# Digital_Input_CPU.net
KiCad netlist of a schematic drawn in Altium Designer
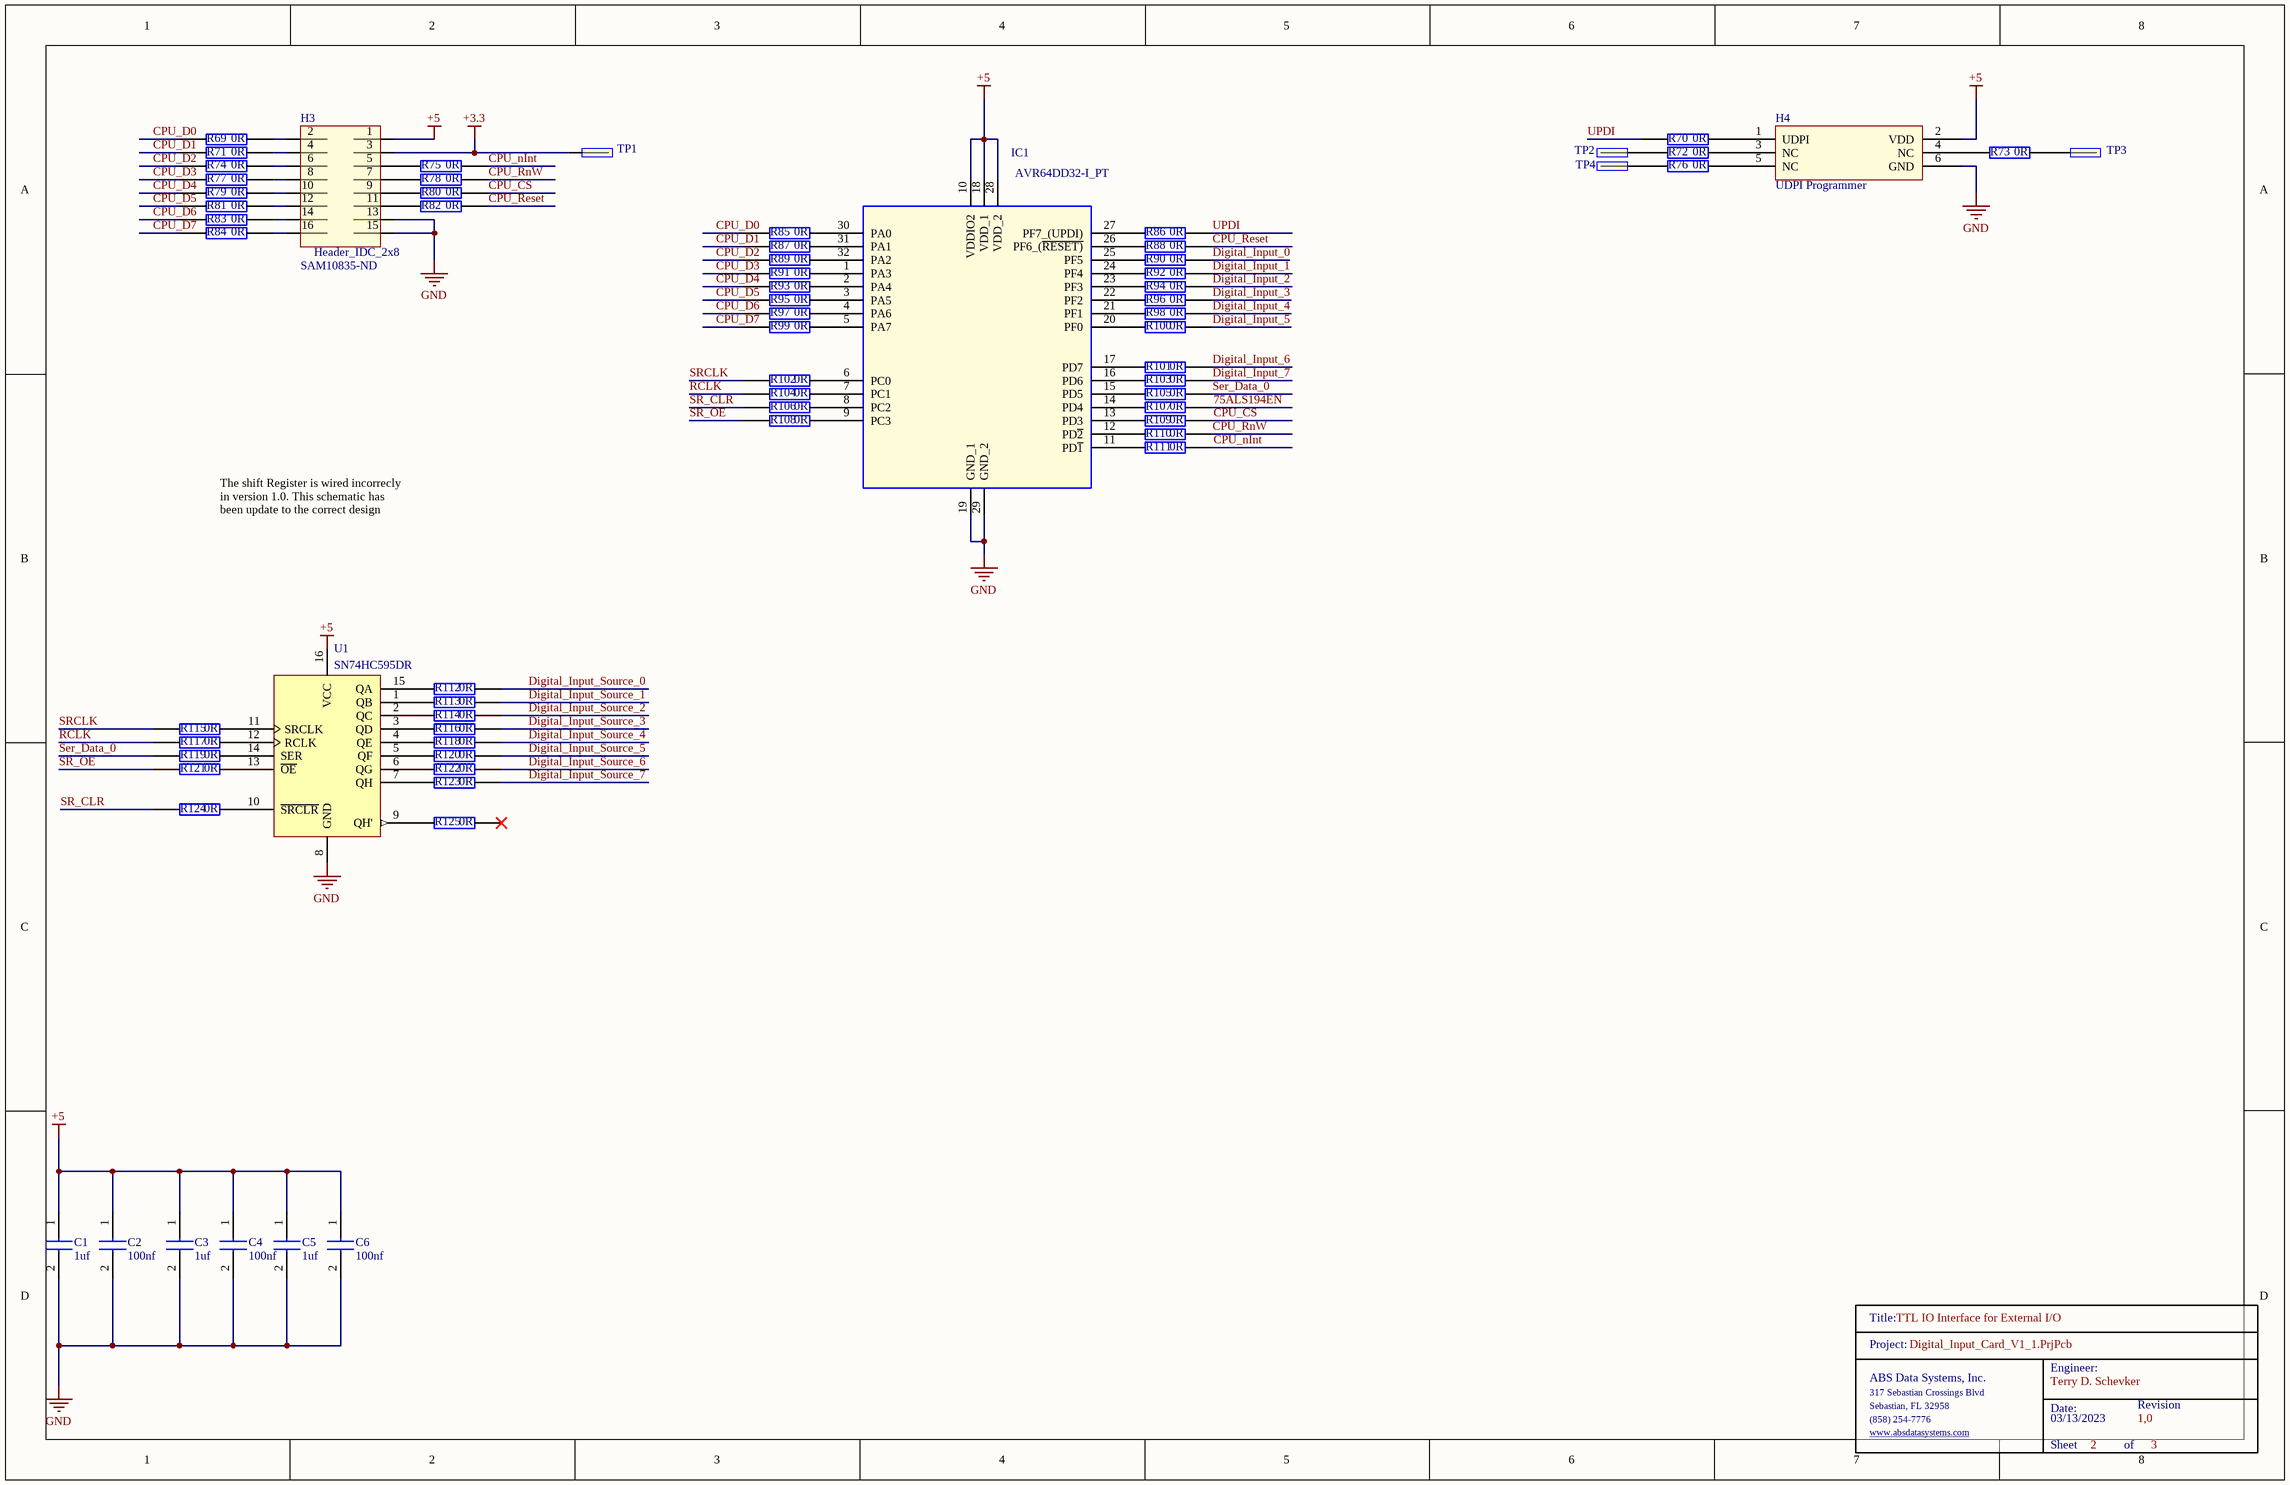
[diagram p0: Digital_Input_CPU.SchDoc]

(export (version "E")
  (design (tool "Eeschema 10.0.6"))
  (components
    (comp (ref "C1")
      (value "1uf")
      (footprint "0603")
      (description "Samsung Electro-Mechanics 0603 1uf")
      (libsource (lib "Capacitors") (part "CL10B105KA8NNNL"))
    )
    (comp (ref "C2")
      (value "100nf")
      (footprint "0603")
      (description "Samsung Electro-Mechanics 0603 100nf")
      (libsource (lib "Capacitors") (part "CL10B104JB8NNNC"))
    )
    (comp (ref "C3")
      (value "1uf")
      (footprint "0603")
      (description "Samsung Electro-Mechanics 0603 1uf")
      (libsource (lib "Capacitors") (part "CL10B105KA8NNNL"))
    )
    (comp (ref "C4")
      (value "100nf")
      (footprint "0603")
      (description "Samsung Electro-Mechanics 0603 100nf")
      (libsource (lib "Capacitors") (part "CL10B104JB8NNNC"))
    )
    (comp (ref "C5")
      (value "1uf")
      (footprint "0603")
      (description "Samsung Electro-Mechanics 0603 1uf")
      (libsource (lib "Capacitors") (part "CL10B105KA8NNNL"))
    )
    (comp (ref "C6")
      (value "100nf")
      (footprint "0603")
      (description "Samsung Electro-Mechanics 0603 100nf")
      (libsource (lib "Capacitors") (part "CL10B104JB8NNNC"))
    )
    (comp (ref "H3")
      (value "Header_IDC_2x8")
      (footprint "HEADER16")
      (description "16 Pin 2x8 Through Hold IDC Connector")
      (fields
        (field (name "MANUFACTURER") "Samtec")
        (field (name "MANUFACTURER PART NUMBER") "TST-108-01-G-D")
        (field (name "SUPPLIER PART NUMBER 1") "SAM10835-ND")
      )
      (libsource (lib "Misc") (part "Header_IDC_2x8"))
    )
    (comp (ref "H4")
      (value "UDPI Programmer")
      (footprint "HDR2X3")
      (description "6 Pin 2X3 Through Hole Header")
      (libsource (lib "Misc") (part "UDPI Programmer"))
    )
    (comp (ref "IC1")
      (value "AVR64DD32-I_PT")
      (footprint "QFP80P900X900X120-32N")
      (description "Integrated Circuit")
      (fields (field (name "MANUFACTURER_PART_NUMBER") "AVR64DD32-I/PT ¦ MULTI-VOLTAGE I/O"))
      (libsource (lib "CPU_Memory") (part "AVR64DD32-I_PT"))
    )
    (comp (ref "R69")
      (value "0R")
      (footprint "0603")
      (description "YAGEO 0603 0 ohm")
      (fields
        (field (name "MOUSER PART NUMBER") "603-RC0603JR-070RL")
        (field (name "MANUFACTURER_PART_NUMBER") "RC0603JR-070RL")
      )
      (libsource (lib "Resistors") (part "RC0603JR-070RL"))
    )
    (comp (ref "R70")
      (value "0R")
      (footprint "0603")
      (description "YAGEO 0603 0 ohm")
      (fields
        (field (name "MOUSER PART NUMBER") "603-RC0603JR-070RL")
        (field (name "MANUFACTURER_PART_NUMBER") "RC0603JR-070RL")
      )
      (libsource (lib "Resistors") (part "RC0603JR-070RL"))
    )
    (comp (ref "R71")
      (value "0R")
      (footprint "0603")
      (description "YAGEO 0603 0 ohm")
      (fields
        (field (name "MOUSER PART NUMBER") "603-RC0603JR-070RL")
        (field (name "MANUFACTURER_PART_NUMBER") "RC0603JR-070RL")
      )
      (libsource (lib "Resistors") (part "RC0603JR-070RL"))
    )
    (comp (ref "R72")
      (value "0R")
      (footprint "0603")
      (description "YAGEO 0603 0 ohm")
      (fields
        (field (name "MOUSER PART NUMBER") "603-RC0603JR-070RL")
        (field (name "MANUFACTURER_PART_NUMBER") "RC0603JR-070RL")
      )
      (libsource (lib "Resistors") (part "RC0603JR-070RL"))
    )
    (comp (ref "R73")
      (value "0R")
      (footprint "0603")
      (description "YAGEO 0603 0 ohm")
      (fields
        (field (name "MOUSER PART NUMBER") "603-RC0603JR-070RL")
        (field (name "MANUFACTURER_PART_NUMBER") "RC0603JR-070RL")
      )
      (libsource (lib "Resistors") (part "RC0603JR-070RL"))
    )
    (comp (ref "R74")
      (value "0R")
      (footprint "0603")
      (description "YAGEO 0603 0 ohm")
      (fields
        (field (name "MOUSER PART NUMBER") "603-RC0603JR-070RL")
        (field (name "MANUFACTURER_PART_NUMBER") "RC0603JR-070RL")
      )
      (libsource (lib "Resistors") (part "RC0603JR-070RL"))
    )
    (comp (ref "R75")
      (value "0R")
      (footprint "0603")
      (description "YAGEO 0603 0 ohm")
      (fields
        (field (name "MOUSER PART NUMBER") "603-RC0603JR-070RL")
        (field (name "MANUFACTURER_PART_NUMBER") "RC0603JR-070RL")
      )
      (libsource (lib "Resistors") (part "RC0603JR-070RL"))
    )
    (comp (ref "R76")
      (value "0R")
      (footprint "0603")
      (description "YAGEO 0603 0 ohm")
      (fields
        (field (name "MOUSER PART NUMBER") "603-RC0603JR-070RL")
        (field (name "MANUFACTURER_PART_NUMBER") "RC0603JR-070RL")
      )
      (libsource (lib "Resistors") (part "RC0603JR-070RL"))
    )
    (comp (ref "R77")
      (value "0R")
      (footprint "0603")
      (description "YAGEO 0603 0 ohm")
      (fields
        (field (name "MOUSER PART NUMBER") "603-RC0603JR-070RL")
        (field (name "MANUFACTURER_PART_NUMBER") "RC0603JR-070RL")
      )
      (libsource (lib "Resistors") (part "RC0603JR-070RL"))
    )
    (comp (ref "R78")
      (value "0R")
      (footprint "0603")
      (description "YAGEO 0603 0 ohm")
      (fields
        (field (name "MOUSER PART NUMBER") "603-RC0603JR-070RL")
        (field (name "MANUFACTURER_PART_NUMBER") "RC0603JR-070RL")
      )
      (libsource (lib "Resistors") (part "RC0603JR-070RL"))
    )
    (comp (ref "R79")
      (value "0R")
      (footprint "0603")
      (description "YAGEO 0603 0 ohm")
      (fields
        (field (name "MOUSER PART NUMBER") "603-RC0603JR-070RL")
        (field (name "MANUFACTURER_PART_NUMBER") "RC0603JR-070RL")
      )
      (libsource (lib "Resistors") (part "RC0603JR-070RL"))
    )
    (comp (ref "R80")
      (value "0R")
      (footprint "0603")
      (description "YAGEO 0603 0 ohm")
      (fields
        (field (name "MOUSER PART NUMBER") "603-RC0603JR-070RL")
        (field (name "MANUFACTURER_PART_NUMBER") "RC0603JR-070RL")
      )
      (libsource (lib "Resistors") (part "RC0603JR-070RL"))
    )
    (comp (ref "R81")
      (value "0R")
      (footprint "0603")
      (description "YAGEO 0603 0 ohm")
      (fields
        (field (name "MOUSER PART NUMBER") "603-RC0603JR-070RL")
        (field (name "MANUFACTURER_PART_NUMBER") "RC0603JR-070RL")
      )
      (libsource (lib "Resistors") (part "RC0603JR-070RL"))
    )
    (comp (ref "R82")
      (value "0R")
      (footprint "0603")
      (description "YAGEO 0603 0 ohm")
      (fields
        (field (name "MOUSER PART NUMBER") "603-RC0603JR-070RL")
        (field (name "MANUFACTURER_PART_NUMBER") "RC0603JR-070RL")
      )
      (libsource (lib "Resistors") (part "RC0603JR-070RL"))
    )
    (comp (ref "R83")
      (value "0R")
      (footprint "0603")
      (description "YAGEO 0603 0 ohm")
      (fields
        (field (name "MOUSER PART NUMBER") "603-RC0603JR-070RL")
        (field (name "MANUFACTURER_PART_NUMBER") "RC0603JR-070RL")
      )
      (libsource (lib "Resistors") (part "RC0603JR-070RL"))
    )
    (comp (ref "R84")
      (value "0R")
      (footprint "0603")
      (description "YAGEO 0603 0 ohm")
      (fields
        (field (name "MOUSER PART NUMBER") "603-RC0603JR-070RL")
        (field (name "MANUFACTURER_PART_NUMBER") "RC0603JR-070RL")
      )
      (libsource (lib "Resistors") (part "RC0603JR-070RL"))
    )
    (comp (ref "R85")
      (value "0R")
      (footprint "0603")
      (description "YAGEO 0603 0 ohm")
      (fields
        (field (name "MOUSER PART NUMBER") "603-RC0603JR-070RL")
        (field (name "MANUFACTURER_PART_NUMBER") "RC0603JR-070RL")
      )
      (libsource (lib "Resistors") (part "RC0603JR-070RL"))
    )
    (comp (ref "R86")
      (value "0R")
      (footprint "0603")
      (description "YAGEO 0603 0 ohm")
      (fields
        (field (name "MOUSER PART NUMBER") "603-RC0603JR-070RL")
        (field (name "MANUFACTURER_PART_NUMBER") "RC0603JR-070RL")
      )
      (libsource (lib "Resistors") (part "RC0603JR-070RL"))
    )
    (comp (ref "R87")
      (value "0R")
      (footprint "0603")
      (description "YAGEO 0603 0 ohm")
      (fields
        (field (name "MOUSER PART NUMBER") "603-RC0603JR-070RL")
        (field (name "MANUFACTURER_PART_NUMBER") "RC0603JR-070RL")
      )
      (libsource (lib "Resistors") (part "RC0603JR-070RL"))
    )
    (comp (ref "R88")
      (value "0R")
      (footprint "0603")
      (description "YAGEO 0603 0 ohm")
      (fields
        (field (name "MOUSER PART NUMBER") "603-RC0603JR-070RL")
        (field (name "MANUFACTURER_PART_NUMBER") "RC0603JR-070RL")
      )
      (libsource (lib "Resistors") (part "RC0603JR-070RL"))
    )
    (comp (ref "R89")
      (value "0R")
      (footprint "0603")
      (description "YAGEO 0603 0 ohm")
      (fields
        (field (name "MOUSER PART NUMBER") "603-RC0603JR-070RL")
        (field (name "MANUFACTURER_PART_NUMBER") "RC0603JR-070RL")
      )
      (libsource (lib "Resistors") (part "RC0603JR-070RL"))
    )
    (comp (ref "R90")
      (value "0R")
      (footprint "0603")
      (description "YAGEO 0603 0 ohm")
      (fields
        (field (name "MOUSER PART NUMBER") "603-RC0603JR-070RL")
        (field (name "MANUFACTURER_PART_NUMBER") "RC0603JR-070RL")
      )
      (libsource (lib "Resistors") (part "RC0603JR-070RL"))
    )
    (comp (ref "R91")
      (value "0R")
      (footprint "0603")
      (description "YAGEO 0603 0 ohm")
      (fields
        (field (name "MOUSER PART NUMBER") "603-RC0603JR-070RL")
        (field (name "MANUFACTURER_PART_NUMBER") "RC0603JR-070RL")
      )
      (libsource (lib "Resistors") (part "RC0603JR-070RL"))
    )
    (comp (ref "R92")
      (value "0R")
      (footprint "0603")
      (description "YAGEO 0603 0 ohm")
      (fields
        (field (name "MOUSER PART NUMBER") "603-RC0603JR-070RL")
        (field (name "MANUFACTURER_PART_NUMBER") "RC0603JR-070RL")
      )
      (libsource (lib "Resistors") (part "RC0603JR-070RL"))
    )
    (comp (ref "R93")
      (value "0R")
      (footprint "0603")
      (description "YAGEO 0603 0 ohm")
      (fields
        (field (name "MOUSER PART NUMBER") "603-RC0603JR-070RL")
        (field (name "MANUFACTURER_PART_NUMBER") "RC0603JR-070RL")
      )
      (libsource (lib "Resistors") (part "RC0603JR-070RL"))
    )
    (comp (ref "R94")
      (value "0R")
      (footprint "0603")
      (description "YAGEO 0603 0 ohm")
      (fields
        (field (name "MOUSER PART NUMBER") "603-RC0603JR-070RL")
        (field (name "MANUFACTURER_PART_NUMBER") "RC0603JR-070RL")
      )
      (libsource (lib "Resistors") (part "RC0603JR-070RL"))
    )
    (comp (ref "R95")
      (value "0R")
      (footprint "0603")
      (description "YAGEO 0603 0 ohm")
      (fields
        (field (name "MOUSER PART NUMBER") "603-RC0603JR-070RL")
        (field (name "MANUFACTURER_PART_NUMBER") "RC0603JR-070RL")
      )
      (libsource (lib "Resistors") (part "RC0603JR-070RL"))
    )
    (comp (ref "R96")
      (value "0R")
      (footprint "0603")
      (description "YAGEO 0603 0 ohm")
      (fields
        (field (name "MOUSER PART NUMBER") "603-RC0603JR-070RL")
        (field (name "MANUFACTURER_PART_NUMBER") "RC0603JR-070RL")
      )
      (libsource (lib "Resistors") (part "RC0603JR-070RL"))
    )
    (comp (ref "R97")
      (value "0R")
      (footprint "0603")
      (description "YAGEO 0603 0 ohm")
      (fields
        (field (name "MOUSER PART NUMBER") "603-RC0603JR-070RL")
        (field (name "MANUFACTURER_PART_NUMBER") "RC0603JR-070RL")
      )
      (libsource (lib "Resistors") (part "RC0603JR-070RL"))
    )
    (comp (ref "R98")
      (value "0R")
      (footprint "0603")
      (description "YAGEO 0603 0 ohm")
      (fields
        (field (name "MOUSER PART NUMBER") "603-RC0603JR-070RL")
        (field (name "MANUFACTURER_PART_NUMBER") "RC0603JR-070RL")
      )
      (libsource (lib "Resistors") (part "RC0603JR-070RL"))
    )
    (comp (ref "R99")
      (value "0R")
      (footprint "0603")
      (description "YAGEO 0603 0 ohm")
      (fields
        (field (name "MOUSER PART NUMBER") "603-RC0603JR-070RL")
        (field (name "MANUFACTURER_PART_NUMBER") "RC0603JR-070RL")
      )
      (libsource (lib "Resistors") (part "RC0603JR-070RL"))
    )
    (comp (ref "R100")
      (value "0R")
      (footprint "0603")
      (description "YAGEO 0603 0 ohm")
      (fields
        (field (name "MOUSER PART NUMBER") "603-RC0603JR-070RL")
        (field (name "MANUFACTURER_PART_NUMBER") "RC0603JR-070RL")
      )
      (libsource (lib "Resistors") (part "RC0603JR-070RL"))
    )
    (comp (ref "R101")
      (value "0R")
      (footprint "0603")
      (description "YAGEO 0603 0 ohm")
      (fields
        (field (name "MOUSER PART NUMBER") "603-RC0603JR-070RL")
        (field (name "MANUFACTURER_PART_NUMBER") "RC0603JR-070RL")
      )
      (libsource (lib "Resistors") (part "RC0603JR-070RL"))
    )
    (comp (ref "R102")
      (value "0R")
      (footprint "0603")
      (description "YAGEO 0603 0 ohm")
      (fields
        (field (name "MOUSER PART NUMBER") "603-RC0603JR-070RL")
        (field (name "MANUFACTURER_PART_NUMBER") "RC0603JR-070RL")
      )
      (libsource (lib "Resistors") (part "RC0603JR-070RL"))
    )
    (comp (ref "R103")
      (value "0R")
      (footprint "0603")
      (description "YAGEO 0603 0 ohm")
      (fields
        (field (name "MOUSER PART NUMBER") "603-RC0603JR-070RL")
        (field (name "MANUFACTURER_PART_NUMBER") "RC0603JR-070RL")
      )
      (libsource (lib "Resistors") (part "RC0603JR-070RL"))
    )
    (comp (ref "R104")
      (value "0R")
      (footprint "0603")
      (description "YAGEO 0603 0 ohm")
      (fields
        (field (name "MOUSER PART NUMBER") "603-RC0603JR-070RL")
        (field (name "MANUFACTURER_PART_NUMBER") "RC0603JR-070RL")
      )
      (libsource (lib "Resistors") (part "RC0603JR-070RL"))
    )
    (comp (ref "R105")
      (value "0R")
      (footprint "0603")
      (description "YAGEO 0603 0 ohm")
      (fields
        (field (name "MOUSER PART NUMBER") "603-RC0603JR-070RL")
        (field (name "MANUFACTURER_PART_NUMBER") "RC0603JR-070RL")
      )
      (libsource (lib "Resistors") (part "RC0603JR-070RL"))
    )
    (comp (ref "R106")
      (value "0R")
      (footprint "0603")
      (description "YAGEO 0603 0 ohm")
      (fields
        (field (name "MOUSER PART NUMBER") "603-RC0603JR-070RL")
        (field (name "MANUFACTURER_PART_NUMBER") "RC0603JR-070RL")
      )
      (libsource (lib "Resistors") (part "RC0603JR-070RL"))
    )
    (comp (ref "R107")
      (value "0R")
      (footprint "0603")
      (description "YAGEO 0603 0 ohm")
      (fields
        (field (name "MOUSER PART NUMBER") "603-RC0603JR-070RL")
        (field (name "MANUFACTURER_PART_NUMBER") "RC0603JR-070RL")
      )
      (libsource (lib "Resistors") (part "RC0603JR-070RL"))
    )
    (comp (ref "R108")
      (value "0R")
      (footprint "0603")
      (description "YAGEO 0603 0 ohm")
      (fields
        (field (name "MOUSER PART NUMBER") "603-RC0603JR-070RL")
        (field (name "MANUFACTURER_PART_NUMBER") "RC0603JR-070RL")
      )
      (libsource (lib "Resistors") (part "RC0603JR-070RL"))
    )
    (comp (ref "R109")
      (value "0R")
      (footprint "0603")
      (description "YAGEO 0603 0 ohm")
      (fields
        (field (name "MOUSER PART NUMBER") "603-RC0603JR-070RL")
        (field (name "MANUFACTURER_PART_NUMBER") "RC0603JR-070RL")
      )
      (libsource (lib "Resistors") (part "RC0603JR-070RL"))
    )
    (comp (ref "R110")
      (value "0R")
      (footprint "0603")
      (description "YAGEO 0603 0 ohm")
      (fields
        (field (name "MOUSER PART NUMBER") "603-RC0603JR-070RL")
        (field (name "MANUFACTURER_PART_NUMBER") "RC0603JR-070RL")
      )
      (libsource (lib "Resistors") (part "RC0603JR-070RL"))
    )
    (comp (ref "R111")
      (value "0R")
      (footprint "0603")
      (description "YAGEO 0603 0 ohm")
      (fields
        (field (name "MOUSER PART NUMBER") "603-RC0603JR-070RL")
        (field (name "MANUFACTURER_PART_NUMBER") "RC0603JR-070RL")
      )
      (libsource (lib "Resistors") (part "RC0603JR-070RL"))
    )
    (comp (ref "R112")
      (value "0R")
      (footprint "0603")
      (description "YAGEO 0603 0 ohm")
      (fields
        (field (name "MOUSER PART NUMBER") "603-RC0603JR-070RL")
        (field (name "MANUFACTURER_PART_NUMBER") "RC0603JR-070RL")
      )
      (libsource (lib "Resistors") (part "RC0603JR-070RL"))
    )
    (comp (ref "R113")
      (value "0R")
      (footprint "0603")
      (description "YAGEO 0603 0 ohm")
      (fields
        (field (name "MOUSER PART NUMBER") "603-RC0603JR-070RL")
        (field (name "MANUFACTURER_PART_NUMBER") "RC0603JR-070RL")
      )
      (libsource (lib "Resistors") (part "RC0603JR-070RL"))
    )
    (comp (ref "R114")
      (value "0R")
      (footprint "0603")
      (description "YAGEO 0603 0 ohm")
      (fields
        (field (name "MOUSER PART NUMBER") "603-RC0603JR-070RL")
        (field (name "MANUFACTURER_PART_NUMBER") "RC0603JR-070RL")
      )
      (libsource (lib "Resistors") (part "RC0603JR-070RL"))
    )
    (comp (ref "R115")
      (value "0R")
      (footprint "0603")
      (description "YAGEO 0603 0 ohm")
      (fields
        (field (name "MOUSER PART NUMBER") "603-RC0603JR-070RL")
        (field (name "MANUFACTURER_PART_NUMBER") "RC0603JR-070RL")
      )
      (libsource (lib "Resistors") (part "RC0603JR-070RL"))
    )
    (comp (ref "R116")
      (value "0R")
      (footprint "0603")
      (description "YAGEO 0603 0 ohm")
      (fields
        (field (name "MOUSER PART NUMBER") "603-RC0603JR-070RL")
        (field (name "MANUFACTURER_PART_NUMBER") "RC0603JR-070RL")
      )
      (libsource (lib "Resistors") (part "RC0603JR-070RL"))
    )
    (comp (ref "R117")
      (value "0R")
      (footprint "0603")
      (description "YAGEO 0603 0 ohm")
      (fields
        (field (name "MOUSER PART NUMBER") "603-RC0603JR-070RL")
        (field (name "MANUFACTURER_PART_NUMBER") "RC0603JR-070RL")
      )
      (libsource (lib "Resistors") (part "RC0603JR-070RL"))
    )
    (comp (ref "R118")
      (value "0R")
      (footprint "0603")
      (description "YAGEO 0603 0 ohm")
      (fields
        (field (name "MOUSER PART NUMBER") "603-RC0603JR-070RL")
        (field (name "MANUFACTURER_PART_NUMBER") "RC0603JR-070RL")
      )
      (libsource (lib "Resistors") (part "RC0603JR-070RL"))
    )
    (comp (ref "R119")
      (value "0R")
      (footprint "0603")
      (description "YAGEO 0603 0 ohm")
      (fields
        (field (name "MOUSER PART NUMBER") "603-RC0603JR-070RL")
        (field (name "MANUFACTURER_PART_NUMBER") "RC0603JR-070RL")
      )
      (libsource (lib "Resistors") (part "RC0603JR-070RL"))
    )
    (comp (ref "R120")
      (value "0R")
      (footprint "0603")
      (description "YAGEO 0603 0 ohm")
      (fields
        (field (name "MOUSER PART NUMBER") "603-RC0603JR-070RL")
        (field (name "MANUFACTURER_PART_NUMBER") "RC0603JR-070RL")
      )
      (libsource (lib "Resistors") (part "RC0603JR-070RL"))
    )
    (comp (ref "R121")
      (value "0R")
      (footprint "0603")
      (description "YAGEO 0603 0 ohm")
      (fields
        (field (name "MOUSER PART NUMBER") "603-RC0603JR-070RL")
        (field (name "MANUFACTURER_PART_NUMBER") "RC0603JR-070RL")
      )
      (libsource (lib "Resistors") (part "RC0603JR-070RL"))
    )
    (comp (ref "R122")
      (value "0R")
      (footprint "0603")
      (description "YAGEO 0603 0 ohm")
      (fields
        (field (name "MOUSER PART NUMBER") "603-RC0603JR-070RL")
        (field (name "MANUFACTURER_PART_NUMBER") "RC0603JR-070RL")
      )
      (libsource (lib "Resistors") (part "RC0603JR-070RL"))
    )
    (comp (ref "R123")
      (value "0R")
      (footprint "0603")
      (description "YAGEO 0603 0 ohm")
      (fields
        (field (name "MOUSER PART NUMBER") "603-RC0603JR-070RL")
        (field (name "MANUFACTURER_PART_NUMBER") "RC0603JR-070RL")
      )
      (libsource (lib "Resistors") (part "RC0603JR-070RL"))
    )
    (comp (ref "R124")
      (value "0R")
      (footprint "0603")
      (description "YAGEO 0603 0 ohm")
      (fields
        (field (name "MOUSER PART NUMBER") "603-RC0603JR-070RL")
        (field (name "MANUFACTURER_PART_NUMBER") "RC0603JR-070RL")
      )
      (libsource (lib "Resistors") (part "RC0603JR-070RL"))
    )
    (comp (ref "R125")
      (value "0R")
      (footprint "0603")
      (description "YAGEO 0603 0 ohm")
      (fields
        (field (name "MOUSER PART NUMBER") "603-RC0603JR-070RL")
        (field (name "MANUFACTURER_PART_NUMBER") "RC0603JR-070RL")
      )
      (libsource (lib "Resistors") (part "RC0603JR-070RL"))
    )
    (comp (ref "TitleBlock_1") (value "TitleBlock") (libsource (lib "Misc") (part "TitleBlock")))
    (comp (ref "TP1")
      (value "TP")
      (footprint "TP")
      (fields
        (field (name "MANUFACTURER") "Samtec")
        (field (name "MANUFACTURER PART NUMBER") "TST-105-01-G-D")
      )
      (libsource (lib "") (part "TP_1"))
    )
    (comp (ref "TP2")
      (value "TP")
      (footprint "TP")
      (fields
        (field (name "MANUFACTURER") "Samtec")
        (field (name "MANUFACTURER PART NUMBER") "TST-105-01-G-D")
      )
      (libsource (lib "Misc") (part "TP"))
    )
    (comp (ref "TP3")
      (value "TP")
      (footprint "TP")
      (fields
        (field (name "MANUFACTURER") "Samtec")
        (field (name "MANUFACTURER PART NUMBER") "TST-105-01-G-D")
      )
      (libsource (lib "") (part "TP_1"))
    )
    (comp (ref "TP4")
      (value "TP")
      (footprint "TP")
      (fields
        (field (name "MANUFACTURER") "Samtec")
        (field (name "MANUFACTURER PART NUMBER") "TST-105-01-G-D")
      )
      (libsource (lib "Misc") (part "TP"))
    )
    (comp (ref "U1")
      (value "SN74HC595DR")
      (footprint "SOIC_16_Narrow")
      (description "8-Bit Shift Registers With 3-State Output Registers, D0016A, LARGE T&R")
      (fields
        (field (name "GENERIC PART NUMBER") "SN74HC595")
        (field (name "MANUFACTURER") "Texas Instruments")
      )
      (libsource (lib "Logic") (part "SN74HC595DR"))
    )
  )
  (nets
    (net (code "1") (name "+3.3") (class "Default")
      (node (ref "H3") (pin "3") (pinfunction "3_3") (pintype "passive"))
      (node (ref "TP1") (pin "1") (pinfunction "1_1") (pintype "passive"))
    )
    (net (code "2") (name "+5") (class "Default")
      (node (ref "C1") (pin "1") (pinfunction "1_1") (pintype "passive"))
      (node (ref "C2") (pin "1") (pinfunction "1_1") (pintype "passive"))
      (node (ref "C3") (pin "1") (pinfunction "1_1") (pintype "passive"))
      (node (ref "C4") (pin "1") (pinfunction "1_1") (pintype "passive"))
      (node (ref "C5") (pin "1") (pinfunction "1_1") (pintype "passive"))
      (node (ref "C6") (pin "1") (pinfunction "1_1") (pintype "passive"))
      (node (ref "H3") (pin "1") (pinfunction "1_1") (pintype "passive"))
      (node (ref "H4") (pin "2") (pinfunction "VDD_2") (pintype "passive"))
      (node (ref "IC1") (pin "10") (pinfunction "VDDIO2_10") (pintype "passive"))
      (node (ref "IC1") (pin "18") (pinfunction "VDD_1_18") (pintype "passive"))
      (node (ref "IC1") (pin "28") (pinfunction "VDD_2_28") (pintype "passive"))
      (node (ref "U1") (pin "16") (pinfunction "VCC_16") (pintype "power_in"))
    )
    (net (code "3") (name "/75ALS194EN") (class "Default")
      (node (ref "R107") (pin "2") (pinfunction "2_2") (pintype "passive"))
    )
    (net (code "4") (name "/CPU_CS") (class "Default")
      (node (ref "R109") (pin "2") (pinfunction "2_2") (pintype "passive"))
      (node (ref "R80") (pin "2") (pinfunction "2_2") (pintype "passive"))
    )
    (net (code "5") (name "/CPU_D0") (class "Default")
      (node (ref "R69") (pin "1") (pinfunction "1_1") (pintype "passive"))
      (node (ref "R85") (pin "1") (pinfunction "1_1") (pintype "passive"))
    )
    (net (code "6") (name "/CPU_D1") (class "Default")
      (node (ref "R71") (pin "1") (pinfunction "1_1") (pintype "passive"))
      (node (ref "R87") (pin "1") (pinfunction "1_1") (pintype "passive"))
    )
    (net (code "7") (name "/CPU_D2") (class "Default")
      (node (ref "R74") (pin "1") (pinfunction "1_1") (pintype "passive"))
      (node (ref "R89") (pin "1") (pinfunction "1_1") (pintype "passive"))
    )
    (net (code "8") (name "/CPU_D3") (class "Default")
      (node (ref "R77") (pin "1") (pinfunction "1_1") (pintype "passive"))
      (node (ref "R91") (pin "1") (pinfunction "1_1") (pintype "passive"))
    )
    (net (code "9") (name "/CPU_D4") (class "Default")
      (node (ref "R79") (pin "1") (pinfunction "1_1") (pintype "passive"))
      (node (ref "R93") (pin "1") (pinfunction "1_1") (pintype "passive"))
    )
    (net (code "10") (name "/CPU_D5") (class "Default")
      (node (ref "R81") (pin "1") (pinfunction "1_1") (pintype "passive"))
      (node (ref "R95") (pin "1") (pinfunction "1_1") (pintype "passive"))
    )
    (net (code "11") (name "/CPU_D6") (class "Default")
      (node (ref "R83") (pin "1") (pinfunction "1_1") (pintype "passive"))
      (node (ref "R97") (pin "1") (pinfunction "1_1") (pintype "passive"))
    )
    (net (code "12") (name "/CPU_D7") (class "Default")
      (node (ref "R84") (pin "1") (pinfunction "1_1") (pintype "passive"))
      (node (ref "R99") (pin "1") (pinfunction "1_1") (pintype "passive"))
    )
    (net (code "13") (name "/CPU_Reset") (class "Default")
      (node (ref "R82") (pin "2") (pinfunction "2_2") (pintype "passive"))
      (node (ref "R88") (pin "2") (pinfunction "2_2") (pintype "passive"))
    )
    (net (code "14") (name "/CPU_RnW") (class "Default")
      (node (ref "R110") (pin "2") (pinfunction "2_2") (pintype "passive"))
      (node (ref "R78") (pin "2") (pinfunction "2_2") (pintype "passive"))
    )
    (net (code "15") (name "/CPU_nInt") (class "Default")
      (node (ref "R111") (pin "2") (pinfunction "2_2") (pintype "passive"))
      (node (ref "R75") (pin "2") (pinfunction "2_2") (pintype "passive"))
    )
    (net (code "16") (name "/Digital_Input_0") (class "Default")
      (node (ref "R90") (pin "2") (pinfunction "2_2") (pintype "passive"))
    )
    (net (code "17") (name "/Digital_Input_1") (class "Default")
      (node (ref "R92") (pin "2") (pinfunction "2_2") (pintype "passive"))
    )
    (net (code "18") (name "/Digital_Input_2") (class "Default")
      (node (ref "R94") (pin "2") (pinfunction "2_2") (pintype "passive"))
    )
    (net (code "19") (name "/Digital_Input_3") (class "Default")
      (node (ref "R96") (pin "2") (pinfunction "2_2") (pintype "passive"))
    )
    (net (code "20") (name "/Digital_Input_4") (class "Default")
      (node (ref "R98") (pin "2") (pinfunction "2_2") (pintype "passive"))
    )
    (net (code "21") (name "/Digital_Input_5") (class "Default")
      (node (ref "R100") (pin "2") (pinfunction "2_2") (pintype "passive"))
    )
    (net (code "22") (name "/Digital_Input_6") (class "Default")
      (node (ref "R101") (pin "2") (pinfunction "2_2") (pintype "passive"))
    )
    (net (code "23") (name "/Digital_Input_7") (class "Default")
      (node (ref "R103") (pin "2") (pinfunction "2_2") (pintype "passive"))
    )
    (net (code "24") (name "/Digital_Input_Source_0") (class "Default")
      (node (ref "R112") (pin "2") (pinfunction "2_2") (pintype "passive"))
    )
    (net (code "25") (name "/Digital_Input_Source_1") (class "Default")
      (node (ref "R113") (pin "2") (pinfunction "2_2") (pintype "passive"))
    )
    (net (code "26") (name "/Digital_Input_Source_2") (class "Default")
      (node (ref "R114") (pin "2") (pinfunction "2_2") (pintype "passive"))
    )
    (net (code "27") (name "/Digital_Input_Source_3") (class "Default")
      (node (ref "R116") (pin "2") (pinfunction "2_2") (pintype "passive"))
    )
    (net (code "28") (name "/Digital_Input_Source_4") (class "Default")
      (node (ref "R118") (pin "2") (pinfunction "2_2") (pintype "passive"))
    )
    (net (code "29") (name "/Digital_Input_Source_5") (class "Default")
      (node (ref "R120") (pin "2") (pinfunction "2_2") (pintype "passive"))
    )
    (net (code "30") (name "/Digital_Input_Source_6") (class "Default")
      (node (ref "R122") (pin "2") (pinfunction "2_2") (pintype "passive"))
    )
    (net (code "31") (name "/Digital_Input_Source_7") (class "Default")
      (node (ref "R123") (pin "2") (pinfunction "2_2") (pintype "passive"))
    )
    (net (code "32") (name "/RCLK") (class "Default")
      (node (ref "R104") (pin "1") (pinfunction "1_1") (pintype "passive"))
      (node (ref "R117") (pin "1") (pinfunction "1_1") (pintype "passive"))
    )
    (net (code "33") (name "/SRCLK") (class "Default")
      (node (ref "R102") (pin "1") (pinfunction "1_1") (pintype "passive"))
      (node (ref "R115") (pin "1") (pinfunction "1_1") (pintype "passive"))
    )
    (net (code "34") (name "/SR_CLR") (class "Default")
      (node (ref "R106") (pin "1") (pinfunction "1_1") (pintype "passive"))
      (node (ref "R124") (pin "1") (pinfunction "1_1") (pintype "passive"))
    )
    (net (code "35") (name "/SR_OE") (class "Default")
      (node (ref "R108") (pin "1") (pinfunction "1_1") (pintype "passive"))
      (node (ref "R121") (pin "1") (pinfunction "1_1") (pintype "passive"))
    )
    (net (code "36") (name "/Ser_Data_0") (class "Default")
      (node (ref "R105") (pin "2") (pinfunction "2_2") (pintype "passive"))
      (node (ref "R119") (pin "1") (pinfunction "1_1") (pintype "passive"))
    )
    (net (code "37") (name "/UPDI") (class "Default")
      (node (ref "R70") (pin "1") (pinfunction "1_1") (pintype "passive"))
      (node (ref "R86") (pin "2") (pinfunction "2_2") (pintype "passive"))
    )
    (net (code "38") (name "GND") (class "Default")
      (node (ref "C1") (pin "2") (pinfunction "2_2") (pintype "passive"))
      (node (ref "C2") (pin "2") (pinfunction "2_2") (pintype "passive"))
      (node (ref "C3") (pin "2") (pinfunction "2_2") (pintype "passive"))
      (node (ref "C4") (pin "2") (pinfunction "2_2") (pintype "passive"))
      (node (ref "C5") (pin "2") (pinfunction "2_2") (pintype "passive"))
      (node (ref "C6") (pin "2") (pinfunction "2_2") (pintype "passive"))
      (node (ref "H3") (pin "13") (pinfunction "13_13") (pintype "passive"))
      (node (ref "H3") (pin "15") (pinfunction "15_15") (pintype "passive"))
      (node (ref "H4") (pin "6") (pinfunction "GND_6") (pintype "passive"))
      (node (ref "IC1") (pin "19") (pinfunction "GND_1_19") (pintype "passive"))
      (node (ref "IC1") (pin "29") (pinfunction "GND_2_29") (pintype "passive"))
      (node (ref "U1") (pin "8") (pinfunction "GND_8") (pintype "power_in"))
    )
    (net (code "39") (name "Net-(H3-Pad2)") (class "Default")
      (node (ref "H3") (pin "2") (pinfunction "2_2") (pintype "passive"))
      (node (ref "R69") (pin "2") (pinfunction "2_2") (pintype "passive"))
    )
    (net (code "40") (name "Net-(H3-Pad4)") (class "Default")
      (node (ref "H3") (pin "4") (pinfunction "4_4") (pintype "passive"))
      (node (ref "R71") (pin "2") (pinfunction "2_2") (pintype "passive"))
    )
    (net (code "41") (name "Net-(H3-Pad5)") (class "Default")
      (node (ref "H3") (pin "5") (pinfunction "5_5") (pintype "passive"))
      (node (ref "R75") (pin "1") (pinfunction "1_1") (pintype "passive"))
    )
    (net (code "42") (name "Net-(H3-Pad6)") (class "Default")
      (node (ref "H3") (pin "6") (pinfunction "6_6") (pintype "passive"))
      (node (ref "R74") (pin "2") (pinfunction "2_2") (pintype "passive"))
    )
    (net (code "43") (name "Net-(H3-Pad7)") (class "Default")
      (node (ref "H3") (pin "7") (pinfunction "7_7") (pintype "passive"))
      (node (ref "R78") (pin "1") (pinfunction "1_1") (pintype "passive"))
    )
    (net (code "44") (name "Net-(H3-Pad8)") (class "Default")
      (node (ref "H3") (pin "8") (pinfunction "8_8") (pintype "passive"))
      (node (ref "R77") (pin "2") (pinfunction "2_2") (pintype "passive"))
    )
    (net (code "45") (name "Net-(H3-Pad9)") (class "Default")
      (node (ref "H3") (pin "9") (pinfunction "9_9") (pintype "passive"))
      (node (ref "R80") (pin "1") (pinfunction "1_1") (pintype "passive"))
    )
    (net (code "46") (name "Net-(H3-Pad10)") (class "Default")
      (node (ref "H3") (pin "10") (pinfunction "10_10") (pintype "passive"))
      (node (ref "R79") (pin "2") (pinfunction "2_2") (pintype "passive"))
    )
    (net (code "47") (name "Net-(H3-Pad11)") (class "Default")
      (node (ref "H3") (pin "11") (pinfunction "11_11") (pintype "passive"))
      (node (ref "R82") (pin "1") (pinfunction "1_1") (pintype "passive"))
    )
    (net (code "48") (name "Net-(H3-Pad12)") (class "Default")
      (node (ref "H3") (pin "12") (pinfunction "12_12") (pintype "passive"))
      (node (ref "R81") (pin "2") (pinfunction "2_2") (pintype "passive"))
    )
    (net (code "49") (name "Net-(H3-Pad14)") (class "Default")
      (node (ref "H3") (pin "14") (pinfunction "14_14") (pintype "passive"))
      (node (ref "R83") (pin "2") (pinfunction "2_2") (pintype "passive"))
    )
    (net (code "50") (name "Net-(H3-Pad16)") (class "Default")
      (node (ref "H3") (pin "16") (pinfunction "16_16") (pintype "passive"))
      (node (ref "R84") (pin "2") (pinfunction "2_2") (pintype "passive"))
    )
    (net (code "51") (name "Net-(H4-NC-Pad3)") (class "Default")
      (node (ref "H4") (pin "3") (pinfunction "NC_3") (pintype "passive"))
      (node (ref "R72") (pin "2") (pinfunction "2_2") (pintype "passive"))
    )
    (net (code "52") (name "Net-(H4-NC-Pad4)") (class "Default")
      (node (ref "H4") (pin "4") (pinfunction "NC_4") (pintype "passive"))
      (node (ref "R73") (pin "1") (pinfunction "1_1") (pintype "passive"))
    )
    (net (code "53") (name "Net-(H4-NC-Pad5)") (class "Default")
      (node (ref "H4") (pin "5") (pinfunction "NC_5") (pintype "passive"))
      (node (ref "R76") (pin "2") (pinfunction "2_2") (pintype "passive"))
    )
    (net (code "54") (name "Net-(H4-UDPI)") (class "Default")
      (node (ref "H4") (pin "1") (pinfunction "UDPI_1") (pintype "passive"))
      (node (ref "R70") (pin "2") (pinfunction "2_2") (pintype "passive"))
    )
    (net (code "55") (name "Net-(IC1-PA0)") (class "Default")
      (node (ref "IC1") (pin "30") (pinfunction "PA0_30") (pintype "passive"))
      (node (ref "R85") (pin "2") (pinfunction "2_2") (pintype "passive"))
    )
    (net (code "56") (name "Net-(IC1-PA1)") (class "Default")
      (node (ref "IC1") (pin "31") (pinfunction "PA1_31") (pintype "passive"))
      (node (ref "R87") (pin "2") (pinfunction "2_2") (pintype "passive"))
    )
    (net (code "57") (name "Net-(IC1-PA2)") (class "Default")
      (node (ref "IC1") (pin "32") (pinfunction "PA2_32") (pintype "passive"))
      (node (ref "R89") (pin "2") (pinfunction "2_2") (pintype "passive"))
    )
    (net (code "58") (name "Net-(IC1-PA3)") (class "Default")
      (node (ref "IC1") (pin "1") (pinfunction "PA3_1") (pintype "passive"))
      (node (ref "R91") (pin "2") (pinfunction "2_2") (pintype "passive"))
    )
    (net (code "59") (name "Net-(IC1-PA4)") (class "Default")
      (node (ref "IC1") (pin "2") (pinfunction "PA4_2") (pintype "passive"))
      (node (ref "R93") (pin "2") (pinfunction "2_2") (pintype "passive"))
    )
    (net (code "60") (name "Net-(IC1-PA5)") (class "Default")
      (node (ref "IC1") (pin "3") (pinfunction "PA5_3") (pintype "passive"))
      (node (ref "R95") (pin "2") (pinfunction "2_2") (pintype "passive"))
    )
    (net (code "61") (name "Net-(IC1-PA6)") (class "Default")
      (node (ref "IC1") (pin "4") (pinfunction "PA6_4") (pintype "passive"))
      (node (ref "R97") (pin "2") (pinfunction "2_2") (pintype "passive"))
    )
    (net (code "62") (name "Net-(IC1-PA7)") (class "Default")
      (node (ref "IC1") (pin "5") (pinfunction "PA7_5") (pintype "passive"))
      (node (ref "R99") (pin "2") (pinfunction "2_2") (pintype "passive"))
    )
    (net (code "63") (name "Net-(IC1-PC0)") (class "Default")
      (node (ref "IC1") (pin "6") (pinfunction "PC0_6") (pintype "passive"))
      (node (ref "R102") (pin "2") (pinfunction "2_2") (pintype "passive"))
    )
    (net (code "64") (name "Net-(IC1-PC1)") (class "Default")
      (node (ref "IC1") (pin "7") (pinfunction "PC1_7") (pintype "passive"))
      (node (ref "R104") (pin "2") (pinfunction "2_2") (pintype "passive"))
    )
    (net (code "65") (name "Net-(IC1-PC2)") (class "Default")
      (node (ref "IC1") (pin "8") (pinfunction "PC2_8") (pintype "passive"))
      (node (ref "R106") (pin "2") (pinfunction "2_2") (pintype "passive"))
    )
    (net (code "66") (name "Net-(IC1-PC3)") (class "Default")
      (node (ref "IC1") (pin "9") (pinfunction "PC3_9") (pintype "passive"))
      (node (ref "R108") (pin "2") (pinfunction "2_2") (pintype "passive"))
    )
    (net (code "67") (name "Net-(IC1-PD3)") (class "Default")
      (node (ref "IC1") (pin "13") (pinfunction "PD3_13") (pintype "passive"))
      (node (ref "R109") (pin "1") (pinfunction "1_1") (pintype "passive"))
    )
    (net (code "68") (name "Net-(IC1-PD4)") (class "Default")
      (node (ref "IC1") (pin "14") (pinfunction "PD4_14") (pintype "passive"))
      (node (ref "R107") (pin "1") (pinfunction "1_1") (pintype "passive"))
    )
    (net (code "69") (name "Net-(IC1-PD5)") (class "Default")
      (node (ref "IC1") (pin "15") (pinfunction "PD5_15") (pintype "passive"))
      (node (ref "R105") (pin "1") (pinfunction "1_1") (pintype "passive"))
    )
    (net (code "70") (name "Net-(IC1-PD6)") (class "Default")
      (node (ref "IC1") (pin "16") (pinfunction "PD6_16") (pintype "passive"))
      (node (ref "R103") (pin "1") (pinfunction "1_1") (pintype "passive"))
    )
    (net (code "71") (name "Net-(IC1-PD7)") (class "Default")
      (node (ref "IC1") (pin "17") (pinfunction "PD7_17") (pintype "passive"))
      (node (ref "R101") (pin "1") (pinfunction "1_1") (pintype "passive"))
    )
    (net (code "72") (name "Net-(IC1-PD~{1})") (class "Default")
      (node (ref "IC1") (pin "11") (pinfunction "PD~{1}_11") (pintype "passive"))
      (node (ref "R111") (pin "1") (pinfunction "1_1") (pintype "passive"))
    )
    (net (code "73") (name "Net-(IC1-PD~{2})") (class "Default")
      (node (ref "IC1") (pin "12") (pinfunction "PD~{2}_12") (pintype "passive"))
      (node (ref "R110") (pin "1") (pinfunction "1_1") (pintype "passive"))
    )
    (net (code "74") (name "Net-(IC1-PF0)") (class "Default")
      (node (ref "IC1") (pin "20") (pinfunction "PF0_20") (pintype "passive"))
      (node (ref "R100") (pin "1") (pinfunction "1_1") (pintype "passive"))
    )
    (net (code "75") (name "Net-(IC1-PF1)") (class "Default")
      (node (ref "IC1") (pin "21") (pinfunction "PF1_21") (pintype "passive"))
      (node (ref "R98") (pin "1") (pinfunction "1_1") (pintype "passive"))
    )
    (net (code "76") (name "Net-(IC1-PF2)") (class "Default")
      (node (ref "IC1") (pin "22") (pinfunction "PF2_22") (pintype "passive"))
      (node (ref "R96") (pin "1") (pinfunction "1_1") (pintype "passive"))
    )
    (net (code "77") (name "Net-(IC1-PF3)") (class "Default")
      (node (ref "IC1") (pin "23") (pinfunction "PF3_23") (pintype "passive"))
      (node (ref "R94") (pin "1") (pinfunction "1_1") (pintype "passive"))
    )
    (net (code "78") (name "Net-(IC1-PF4)") (class "Default")
      (node (ref "IC1") (pin "24") (pinfunction "PF4_24") (pintype "passive"))
      (node (ref "R92") (pin "1") (pinfunction "1_1") (pintype "passive"))
    )
    (net (code "79") (name "Net-(IC1-PF5)") (class "Default")
      (node (ref "IC1") (pin "25") (pinfunction "PF5_25") (pintype "passive"))
      (node (ref "R90") (pin "1") (pinfunction "1_1") (pintype "passive"))
    )
    (net (code "80") (name "Net-(IC1-PF6_(~{RESET)})") (class "Default")
      (node (ref "IC1") (pin "26") (pinfunction "PF6_(~{RESET)}_26") (pintype "passive"))
      (node (ref "R88") (pin "1") (pinfunction "1_1") (pintype "passive"))
    )
    (net (code "81") (name "Net-(IC1-PF7_(UPDI))") (class "Default")
      (node (ref "IC1") (pin "27") (pinfunction "PF7_(UPDI)_27") (pintype "passive"))
      (node (ref "R86") (pin "1") (pinfunction "1_1") (pintype "passive"))
    )
    (net (code "82") (name "Net-(R72-Pad1)") (class "Default")
      (node (ref "R72") (pin "1") (pinfunction "1_1") (pintype "passive"))
      (node (ref "TP2") (pin "1") (pinfunction "1_1") (pintype "passive"))
    )
    (net (code "83") (name "Net-(R73-Pad2)") (class "Default")
      (node (ref "R73") (pin "2") (pinfunction "2_2") (pintype "passive"))
      (node (ref "TP3") (pin "1") (pinfunction "1_1") (pintype "passive"))
    )
    (net (code "84") (name "Net-(R76-Pad1)") (class "Default")
      (node (ref "R76") (pin "1") (pinfunction "1_1") (pintype "passive"))
      (node (ref "TP4") (pin "1") (pinfunction "1_1") (pintype "passive"))
    )
    (net (code "85") (name "Net-(U1-QA)") (class "Default")
      (node (ref "R112") (pin "1") (pinfunction "1_1") (pintype "passive"))
      (node (ref "U1") (pin "15") (pinfunction "QA_15") (pintype "tri_state"))
    )
    (net (code "86") (name "Net-(U1-QB)") (class "Default")
      (node (ref "R113") (pin "1") (pinfunction "1_1") (pintype "passive"))
      (node (ref "U1") (pin "1") (pinfunction "QB_1") (pintype "tri_state"))
    )
    (net (code "87") (name "Net-(U1-QC)") (class "Default")
      (node (ref "R114") (pin "1") (pinfunction "1_1") (pintype "passive"))
      (node (ref "U1") (pin "2") (pinfunction "QC_2") (pintype "tri_state"))
    )
    (net (code "88") (name "Net-(U1-QD)") (class "Default")
      (node (ref "R116") (pin "1") (pinfunction "1_1") (pintype "passive"))
      (node (ref "U1") (pin "3") (pinfunction "QD_3") (pintype "tri_state"))
    )
    (net (code "89") (name "Net-(U1-QE)") (class "Default")
      (node (ref "R118") (pin "1") (pinfunction "1_1") (pintype "passive"))
      (node (ref "U1") (pin "4") (pinfunction "QE_4") (pintype "tri_state"))
    )
    (net (code "90") (name "Net-(U1-QF)") (class "Default")
      (node (ref "R120") (pin "1") (pinfunction "1_1") (pintype "passive"))
      (node (ref "U1") (pin "5") (pinfunction "QF_5") (pintype "tri_state"))
    )
    (net (code "91") (name "Net-(U1-QG)") (class "Default")
      (node (ref "R122") (pin "1") (pinfunction "1_1") (pintype "passive"))
      (node (ref "U1") (pin "6") (pinfunction "QG_6") (pintype "tri_state"))
    )
    (net (code "92") (name "Net-(U1-QH')") (class "Default")
      (node (ref "R125") (pin "1") (pinfunction "1_1") (pintype "passive"))
      (node (ref "U1") (pin "9") (pinfunction "QH'_9") (pintype "output"))
    )
    (net (code "93") (name "Net-(U1-QH)") (class "Default")
      (node (ref "R123") (pin "1") (pinfunction "1_1") (pintype "passive"))
      (node (ref "U1") (pin "7") (pinfunction "QH_7") (pintype "tri_state"))
    )
    (net (code "94") (name "Net-(U1-RCLK)") (class "Default")
      (node (ref "R117") (pin "2") (pinfunction "2_2") (pintype "passive"))
      (node (ref "U1") (pin "12") (pinfunction "RCLK_12") (pintype "passive"))
    )
    (net (code "95") (name "Net-(U1-SER)") (class "Default")
      (node (ref "R119") (pin "2") (pinfunction "2_2") (pintype "passive"))
      (node (ref "U1") (pin "14") (pinfunction "SER_14") (pintype "passive"))
    )
    (net (code "96") (name "Net-(U1-SRCLK)") (class "Default")
      (node (ref "R115") (pin "2") (pinfunction "2_2") (pintype "passive"))
      (node (ref "U1") (pin "11") (pinfunction "SRCLK_11") (pintype "passive"))
    )
    (net (code "97") (name "Net-(U1-~{OE})") (class "Default")
      (node (ref "R121") (pin "2") (pinfunction "2_2") (pintype "passive"))
      (node (ref "U1") (pin "13") (pinfunction "~{OE}_13") (pintype "passive"))
    )
    (net (code "98") (name "Net-(U1-~{SRCLR})") (class "Default")
      (node (ref "R124") (pin "2") (pinfunction "2_2") (pintype "passive"))
      (node (ref "U1") (pin "10") (pinfunction "~{SRCLR}_10") (pintype "passive"))
    )
    (net (code "99") (name "unconnected-(R125-Pad2)") (class "Default")
      (node (ref "R125") (pin "2") (pinfunction "2_2") (pintype "passive+no_connect"))
    )
  )
)
